# stm32-shield.net
KiCad netlist of a schematic drawn in EAGLE
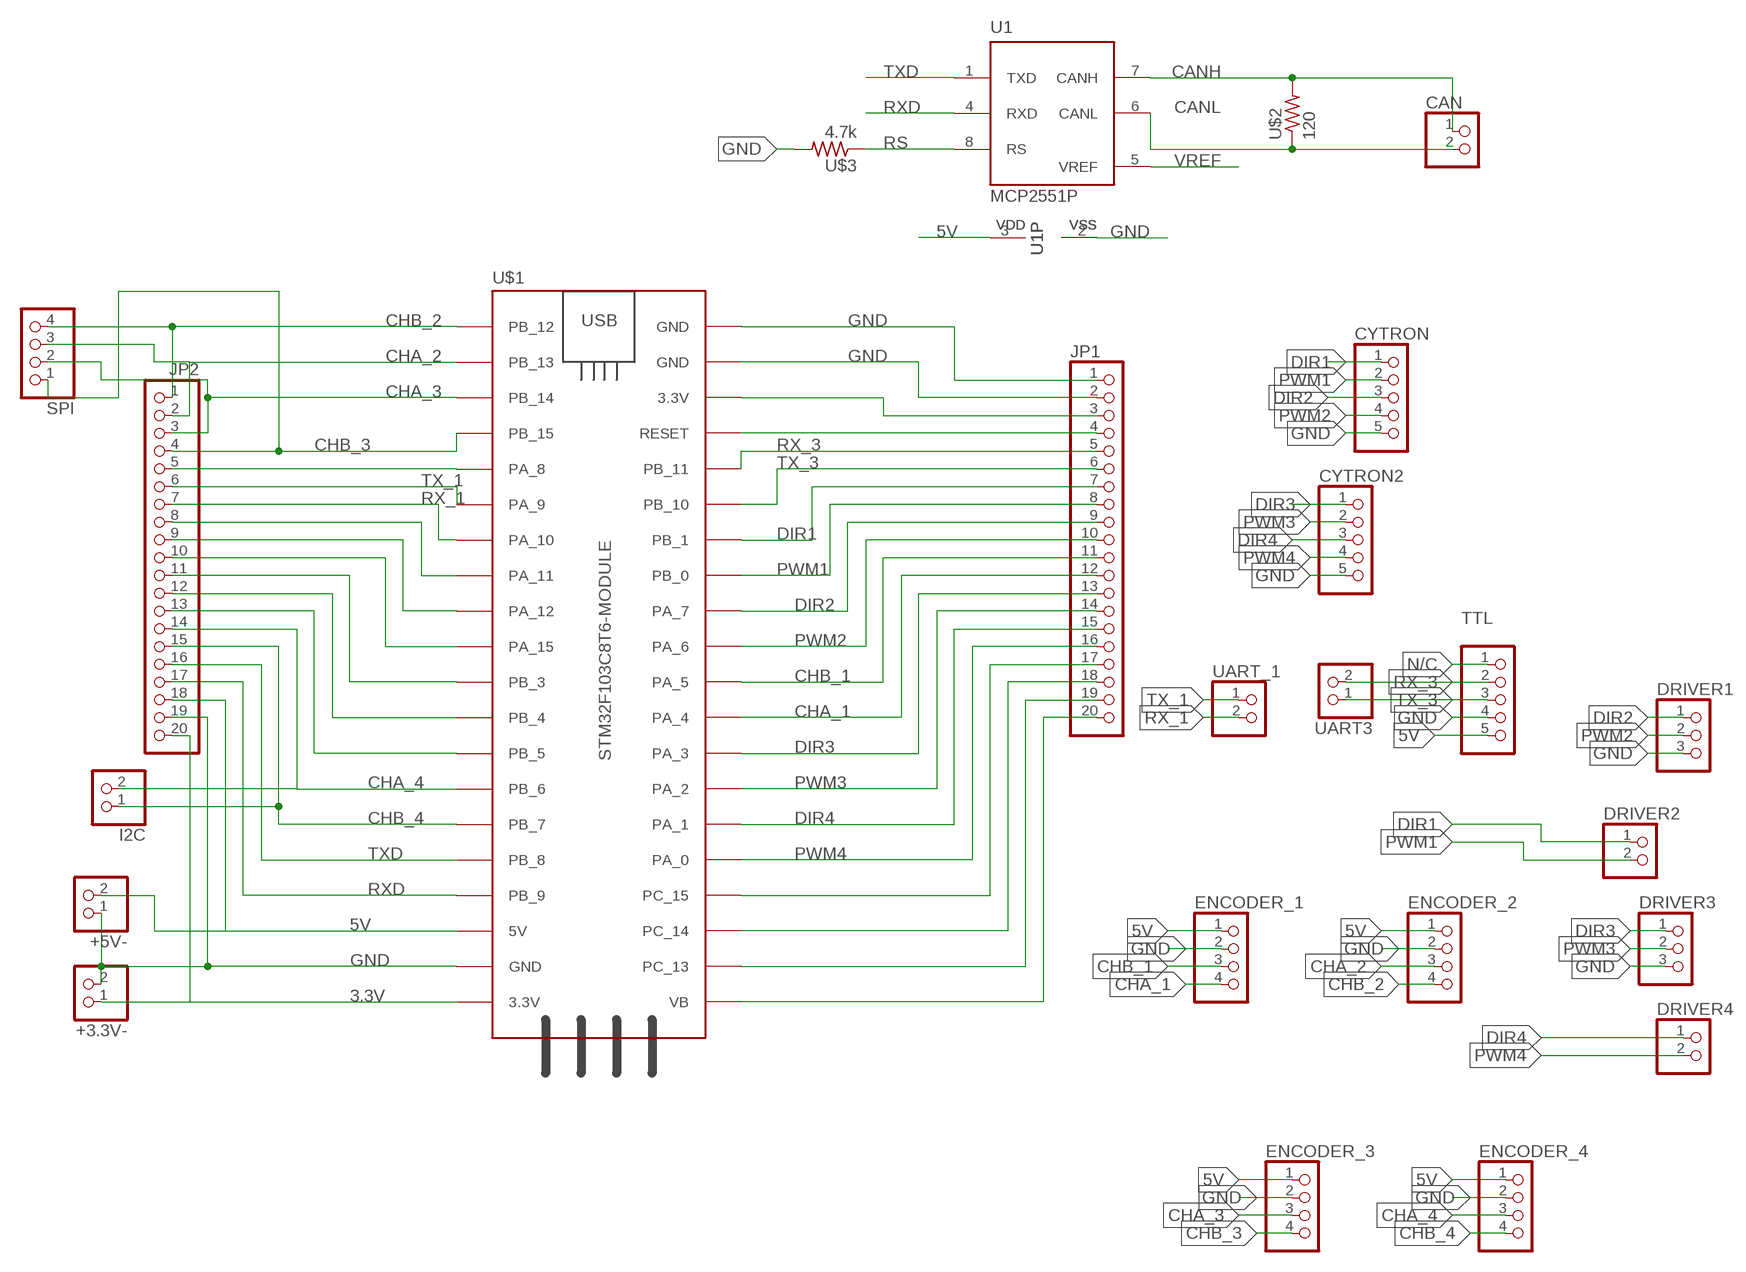
[diagram p0: schematic, sheet 1]

(export (version "E")
  (design (tool "Eeschema 10.0.6"))
  (components
    (comp (ref "+3.3V-")
      (value "PINHD-2_DATA")
      (footprint "eagle-import:1X02_DATA")
      (libsource (lib "eagle-import") (part "PINHD-2_DATA"))
    )
    (comp (ref "+5V-")
      (value "PINHD-2_DATA")
      (footprint "eagle-import:1X02_DATA")
      (libsource (lib "eagle-import") (part "PINHD-2_DATA"))
    )
    (comp (ref "CAN")
      (value "PINHD-2_DATA")
      (footprint "eagle-import:1X02_DATA")
      (libsource (lib "eagle-import") (part "PINHD-2_DATA"))
    )
    (comp (ref "CYTRON")
      (value "PINHD-5_DATA")
      (footprint "eagle-import:1X05_DATA")
      (libsource (lib "eagle-import") (part "PINHD-5_DATA"))
    )
    (comp (ref "CYTRON2")
      (value "PINHD-5_DATA")
      (footprint "eagle-import:1X05_DATA")
      (libsource (lib "eagle-import") (part "PINHD-5_DATA"))
    )
    (comp (ref "DRIVER1")
      (value "PINHD-3_DATA")
      (footprint "eagle-import:1X03_DATA")
      (libsource (lib "eagle-import") (part "PINHD-3_DATA"))
    )
    (comp (ref "DRIVER2")
      (value "PINHD-2_DATA")
      (footprint "eagle-import:1X02_DATA")
      (libsource (lib "eagle-import") (part "PINHD-2_DATA"))
    )
    (comp (ref "DRIVER3")
      (value "PINHD-3_DATA")
      (footprint "eagle-import:1X03_DATA")
      (libsource (lib "eagle-import") (part "PINHD-3_DATA"))
    )
    (comp (ref "DRIVER4")
      (value "PINHD-2_DATA")
      (footprint "eagle-import:1X02_DATA")
      (libsource (lib "eagle-import") (part "PINHD-2_DATA"))
    )
    (comp (ref "ENCODER_1")
      (value "PINHD-4_DATA")
      (footprint "eagle-import:1X04_DATA")
      (libsource (lib "eagle-import") (part "PINHD-4_DATA"))
    )
    (comp (ref "ENCODER_2")
      (value "PINHD-4_DATA")
      (footprint "eagle-import:1X04_DATA")
      (libsource (lib "eagle-import") (part "PINHD-4_DATA"))
    )
    (comp (ref "ENCODER_3")
      (value "PINHD-4_DATA")
      (footprint "eagle-import:1X04_DATA")
      (libsource (lib "eagle-import") (part "PINHD-4_DATA"))
    )
    (comp (ref "ENCODER_4")
      (value "PINHD-4_DATA")
      (footprint "eagle-import:1X04_DATA")
      (libsource (lib "eagle-import") (part "PINHD-4_DATA"))
    )
    (comp (ref "I2C")
      (value "PINHD-2_DATA")
      (footprint "eagle-import:1X02_DATA")
      (libsource (lib "eagle-import") (part "PINHD-2_DATA"))
    )
    (comp (ref "JP1")
      (value "PINHD-1X20")
      (footprint "eagle-import:1X20")
      (libsource (lib "eagle-import") (part "PINHD-1X20"))
    )
    (comp (ref "JP2")
      (value "PINHD-1X20")
      (footprint "eagle-import:1X20")
      (libsource (lib "eagle-import") (part "PINHD-1X20"))
    )
    (comp (ref "SPI")
      (value "PINHD-4_DATA")
      (footprint "eagle-import:1X04_DATA")
      (libsource (lib "eagle-import") (part "PINHD-4_DATA"))
    )
    (comp (ref "TTL")
      (value "PINHD-5_DATA")
      (footprint "eagle-import:1X05_DATA")
      (libsource (lib "eagle-import") (part "PINHD-5_DATA"))
    )
    (comp (ref "U$1")
      (value "STM32F103C8T6-MODULE")
      (footprint "eagle-import:STM32F103C8T6-MODULE")
      (libsource (lib "eagle-import") (part "STM32F103C8T6-MODULE"))
    )
    (comp (ref "U$2")
      (value "120")
      (footprint "eagle-import:0204_7")
      (libsource (lib "eagle-import") (part "RES-7"))
    )
    (comp (ref "U$3")
      (value "4.7k")
      (footprint "eagle-import:0204_7")
      (libsource (lib "eagle-import") (part "RES-7"))
    )
    (comp (ref "U1")
      (value "MCP2551P")
      (footprint "eagle-import:DIL8")
      (libsource (lib "eagle-import") (part "MCP2551P"))
    )
    (comp (ref "UART3")
      (value "PINHD-2_DATA")
      (footprint "eagle-import:1X02_DATA")
      (libsource (lib "eagle-import") (part "PINHD-2_DATA"))
    )
    (comp (ref "UART_1")
      (value "PINHD-2_DATA")
      (footprint "eagle-import:1X02_DATA")
      (libsource (lib "eagle-import") (part "PINHD-2_DATA"))
    )
  )
  (nets
    (net (code "1") (name "/3.3V") (class "Default")
      (node (ref "+3.3V-") (pin "1") (pinfunction "1_1") (pintype "passive"))
      (node (ref "JP2") (pin "20") (pinfunction "20_20") (pintype "passive"))
      (node (ref "U$1") (pin "3.3V_1") (pinfunction "3.3V_3.3V_1") (pintype "bidirectional"))
    )
    (net (code "2") (name "/CANH") (class "Default")
      (node (ref "CAN") (pin "1") (pinfunction "1_1") (pintype "passive"))
      (node (ref "U$2") (pin "2") (pinfunction "2_2") (pintype "passive"))
      (node (ref "U1") (pin "7") (pinfunction "CANH_7") (pintype "bidirectional"))
    )
    (net (code "3") (name "/CANL") (class "Default")
      (node (ref "CAN") (pin "2") (pinfunction "2_2") (pintype "passive"))
      (node (ref "U$2") (pin "1") (pinfunction "1_1") (pintype "passive"))
      (node (ref "U1") (pin "6") (pinfunction "CANL_6") (pintype "bidirectional"))
    )
    (net (code "4") (name "/RS") (class "Default")
      (node (ref "U$3") (pin "1") (pinfunction "1_1") (pintype "passive"))
      (node (ref "U1") (pin "8") (pinfunction "RS_8") (pintype "input"))
    )
    (net (code "5") (name "/RXD") (class "Default")
      (node (ref "JP2") (pin "17") (pinfunction "17_17") (pintype "passive"))
      (node (ref "U$1") (pin "PB_9") (pinfunction "PB_9_PB_9") (pintype "bidirectional"))
      (node (ref "U1") (pin "4") (pinfunction "RXD_4") (pintype "output"))
    )
    (net (code "6") (name "/TXD") (class "Default")
      (node (ref "JP2") (pin "16") (pinfunction "16_16") (pintype "passive"))
      (node (ref "U$1") (pin "PB_8") (pinfunction "PB_8_PB_8") (pintype "bidirectional"))
      (node (ref "U1") (pin "1") (pinfunction "TXD_1") (pintype "input"))
    )
    (net (code "7") (name "/VREF") (class "Default")
      (node (ref "U1") (pin "5") (pinfunction "VREF_5") (pintype "power_in"))
    )
    (net (code "8") (name "5V") (class "Default")
      (node (ref "+5V-") (pin "2") (pinfunction "2_2") (pintype "passive"))
      (node (ref "ENCODER_1") (pin "1") (pinfunction "1_1") (pintype "passive"))
      (node (ref "ENCODER_2") (pin "1") (pinfunction "1_1") (pintype "passive"))
      (node (ref "ENCODER_3") (pin "1") (pinfunction "1_1") (pintype "passive"))
      (node (ref "ENCODER_4") (pin "1") (pinfunction "1_1") (pintype "passive"))
      (node (ref "JP2") (pin "18") (pinfunction "18_18") (pintype "passive"))
      (node (ref "TTL") (pin "5") (pinfunction "5_5") (pintype "passive"))
      (node (ref "U$1") (pin "5V") (pinfunction "5V_5V") (pintype "bidirectional"))
      (node (ref "U1") (pin "3") (pinfunction "VDD_3") (pintype "power_in"))
    )
    (net (code "9") (name "CHA_1") (class "Default")
      (node (ref "ENCODER_1") (pin "4") (pinfunction "4_4") (pintype "passive"))
      (node (ref "JP1") (pin "12") (pinfunction "12_12") (pintype "passive"))
      (node (ref "U$1") (pin "PA_4") (pinfunction "PA_4_PA_4") (pintype "bidirectional"))
    )
    (net (code "10") (name "CHA_2") (class "Default")
      (node (ref "ENCODER_2") (pin "3") (pinfunction "3_3") (pintype "passive"))
      (node (ref "JP2") (pin "2") (pinfunction "2_2") (pintype "passive"))
      (node (ref "SPI") (pin "3") (pinfunction "3_3") (pintype "passive"))
      (node (ref "U$1") (pin "PB_13") (pinfunction "PB_13_PB_13") (pintype "bidirectional"))
    )
    (net (code "11") (name "CHA_3") (class "Default")
      (node (ref "ENCODER_3") (pin "3") (pinfunction "3_3") (pintype "passive"))
      (node (ref "JP2") (pin "3") (pinfunction "3_3") (pintype "passive"))
      (node (ref "SPI") (pin "2") (pinfunction "2_2") (pintype "passive"))
      (node (ref "U$1") (pin "PB_14") (pinfunction "PB_14_PB_14") (pintype "bidirectional"))
    )
    (net (code "12") (name "CHA_4") (class "Default")
      (node (ref "ENCODER_4") (pin "3") (pinfunction "3_3") (pintype "passive"))
      (node (ref "I2C") (pin "2") (pinfunction "2_2") (pintype "passive"))
      (node (ref "JP2") (pin "14") (pinfunction "14_14") (pintype "passive"))
      (node (ref "U$1") (pin "PB_6") (pinfunction "PB_6_PB_6") (pintype "bidirectional"))
    )
    (net (code "13") (name "CHB_1") (class "Default")
      (node (ref "ENCODER_1") (pin "3") (pinfunction "3_3") (pintype "passive"))
      (node (ref "JP1") (pin "11") (pinfunction "11_11") (pintype "passive"))
      (node (ref "U$1") (pin "PA_5") (pinfunction "PA_5_PA_5") (pintype "bidirectional"))
    )
    (net (code "14") (name "CHB_2") (class "Default")
      (node (ref "ENCODER_2") (pin "4") (pinfunction "4_4") (pintype "passive"))
      (node (ref "JP2") (pin "1") (pinfunction "1_1") (pintype "passive"))
      (node (ref "SPI") (pin "4") (pinfunction "4_4") (pintype "passive"))
      (node (ref "U$1") (pin "PB_12") (pinfunction "PB_12_PB_12") (pintype "bidirectional"))
    )
    (net (code "15") (name "CHB_3") (class "Default")
      (node (ref "ENCODER_3") (pin "4") (pinfunction "4_4") (pintype "passive"))
      (node (ref "JP2") (pin "4") (pinfunction "4_4") (pintype "passive"))
      (node (ref "SPI") (pin "1") (pinfunction "1_1") (pintype "passive"))
      (node (ref "U$1") (pin "PB_15") (pinfunction "PB_15_PB_15") (pintype "bidirectional"))
    )
    (net (code "16") (name "CHB_4") (class "Default")
      (node (ref "ENCODER_4") (pin "4") (pinfunction "4_4") (pintype "passive"))
      (node (ref "I2C") (pin "1") (pinfunction "1_1") (pintype "passive"))
      (node (ref "JP2") (pin "15") (pinfunction "15_15") (pintype "passive"))
      (node (ref "U$1") (pin "PB_7") (pinfunction "PB_7_PB_7") (pintype "bidirectional"))
    )
    (net (code "17") (name "DIR1") (class "Default")
      (node (ref "CYTRON") (pin "1") (pinfunction "1_1") (pintype "passive"))
      (node (ref "DRIVER2") (pin "1") (pinfunction "1_1") (pintype "passive"))
      (node (ref "JP1") (pin "7") (pinfunction "7_7") (pintype "passive"))
      (node (ref "U$1") (pin "PB_1") (pinfunction "PB_1_PB_1") (pintype "bidirectional"))
    )
    (net (code "18") (name "DIR2") (class "Default")
      (node (ref "CYTRON") (pin "3") (pinfunction "3_3") (pintype "passive"))
      (node (ref "DRIVER1") (pin "1") (pinfunction "1_1") (pintype "passive"))
      (node (ref "JP1") (pin "9") (pinfunction "9_9") (pintype "passive"))
      (node (ref "U$1") (pin "PA_7") (pinfunction "PA_7_PA_7") (pintype "bidirectional"))
    )
    (net (code "19") (name "DIR3") (class "Default")
      (node (ref "CYTRON2") (pin "1") (pinfunction "1_1") (pintype "passive"))
      (node (ref "DRIVER3") (pin "1") (pinfunction "1_1") (pintype "passive"))
      (node (ref "JP1") (pin "13") (pinfunction "13_13") (pintype "passive"))
      (node (ref "U$1") (pin "PA_3") (pinfunction "PA_3_PA_3") (pintype "bidirectional"))
    )
    (net (code "20") (name "DIR4") (class "Default")
      (node (ref "CYTRON2") (pin "3") (pinfunction "3_3") (pintype "passive"))
      (node (ref "DRIVER4") (pin "1") (pinfunction "1_1") (pintype "passive"))
      (node (ref "JP1") (pin "15") (pinfunction "15_15") (pintype "passive"))
      (node (ref "U$1") (pin "PA_1") (pinfunction "PA_1_PA_1") (pintype "bidirectional"))
    )
    (net (code "21") (name "GND") (class "Default")
      (node (ref "+3.3V-") (pin "2") (pinfunction "2_2") (pintype "passive"))
      (node (ref "+5V-") (pin "1") (pinfunction "1_1") (pintype "passive"))
      (node (ref "CYTRON") (pin "5") (pinfunction "5_5") (pintype "passive"))
      (node (ref "CYTRON2") (pin "5") (pinfunction "5_5") (pintype "passive"))
      (node (ref "DRIVER1") (pin "3") (pinfunction "3_3") (pintype "passive"))
      (node (ref "DRIVER3") (pin "3") (pinfunction "3_3") (pintype "passive"))
      (node (ref "ENCODER_1") (pin "2") (pinfunction "2_2") (pintype "passive"))
      (node (ref "ENCODER_2") (pin "2") (pinfunction "2_2") (pintype "passive"))
      (node (ref "ENCODER_3") (pin "2") (pinfunction "2_2") (pintype "passive"))
      (node (ref "ENCODER_4") (pin "2") (pinfunction "2_2") (pintype "passive"))
      (node (ref "JP1") (pin "1") (pinfunction "1_1") (pintype "passive"))
      (node (ref "JP1") (pin "2") (pinfunction "2_2") (pintype "passive"))
      (node (ref "JP2") (pin "19") (pinfunction "19_19") (pintype "passive"))
      (node (ref "TTL") (pin "4") (pinfunction "4_4") (pintype "passive"))
      (node (ref "U$1") (pin "GND_1") (pinfunction "GND_GND_1") (pintype "bidirectional"))
      (node (ref "U$1") (pin "GND_2") (pinfunction "GND_GND_2") (pintype "bidirectional"))
      (node (ref "U$1") (pin "GND_3") (pinfunction "GND_GND_3") (pintype "power_in"))
      (node (ref "U$3") (pin "2") (pinfunction "2_2") (pintype "passive"))
      (node (ref "U1") (pin "2") (pinfunction "VSS_2") (pintype "power_in"))
    )
    (net (code "22") (name "Net-(JP1-Pad3)") (class "Default")
      (node (ref "JP1") (pin "3") (pinfunction "3_3") (pintype "passive"))
      (node (ref "U$1") (pin "3.3V_2") (pinfunction "3.3V_3.3V_2") (pintype "bidirectional"))
    )
    (net (code "23") (name "Net-(JP1-Pad4)") (class "Default")
      (node (ref "JP1") (pin "4") (pinfunction "4_4") (pintype "passive"))
      (node (ref "U$1") (pin "RESET") (pinfunction "RESET_RESET") (pintype "bidirectional"))
    )
    (net (code "24") (name "Net-(JP1-Pad17)") (class "Default")
      (node (ref "JP1") (pin "17") (pinfunction "17_17") (pintype "passive"))
      (node (ref "U$1") (pin "PC_15") (pinfunction "PC_15_PC_15") (pintype "bidirectional"))
    )
    (net (code "25") (name "Net-(JP1-Pad18)") (class "Default")
      (node (ref "JP1") (pin "18") (pinfunction "18_18") (pintype "passive"))
      (node (ref "U$1") (pin "PC_14") (pinfunction "PC_14_PC_14") (pintype "bidirectional"))
    )
    (net (code "26") (name "Net-(JP1-Pad19)") (class "Default")
      (node (ref "JP1") (pin "19") (pinfunction "19_19") (pintype "passive"))
      (node (ref "U$1") (pin "PC_13") (pinfunction "PC_13_PC_13") (pintype "bidirectional"))
    )
    (net (code "27") (name "Net-(JP1-Pad20)") (class "Default")
      (node (ref "JP1") (pin "20") (pinfunction "20_20") (pintype "passive"))
      (node (ref "U$1") (pin "VB") (pinfunction "VB_VB") (pintype "bidirectional"))
    )
    (net (code "28") (name "Net-(JP2-Pad5)") (class "Default")
      (node (ref "JP2") (pin "5") (pinfunction "5_5") (pintype "passive"))
      (node (ref "U$1") (pin "PA_8") (pinfunction "PA_8_PA_8") (pintype "bidirectional"))
    )
    (net (code "29") (name "Net-(JP2-Pad8)") (class "Default")
      (node (ref "JP2") (pin "8") (pinfunction "8_8") (pintype "passive"))
      (node (ref "U$1") (pin "PA_11") (pinfunction "PA_11_PA_11") (pintype "bidirectional"))
    )
    (net (code "30") (name "Net-(JP2-Pad9)") (class "Default")
      (node (ref "JP2") (pin "9") (pinfunction "9_9") (pintype "passive"))
      (node (ref "U$1") (pin "PA_12") (pinfunction "PA_12_PA_12") (pintype "bidirectional"))
    )
    (net (code "31") (name "Net-(JP2-Pad10)") (class "Default")
      (node (ref "JP2") (pin "10") (pinfunction "10_10") (pintype "passive"))
      (node (ref "U$1") (pin "PA_15") (pinfunction "PA_15_PA_15") (pintype "bidirectional"))
    )
    (net (code "32") (name "Net-(JP2-Pad11)") (class "Default")
      (node (ref "JP2") (pin "11") (pinfunction "11_11") (pintype "passive"))
      (node (ref "U$1") (pin "PB_3") (pinfunction "PB_3_PB_3") (pintype "bidirectional"))
    )
    (net (code "33") (name "Net-(JP2-Pad12)") (class "Default")
      (node (ref "JP2") (pin "12") (pinfunction "12_12") (pintype "passive"))
      (node (ref "U$1") (pin "PB_4") (pinfunction "PB_4_PB_4") (pintype "bidirectional"))
    )
    (net (code "34") (name "Net-(JP2-Pad13)") (class "Default")
      (node (ref "JP2") (pin "13") (pinfunction "13_13") (pintype "passive"))
      (node (ref "U$1") (pin "PB_5") (pinfunction "PB_5_PB_5") (pintype "bidirectional"))
    )
    (net (code "35") (name "N{slash}C") (class "Default")
      (node (ref "TTL") (pin "1") (pinfunction "1_1") (pintype "passive"))
    )
    (net (code "36") (name "PWM1") (class "Default")
      (node (ref "CYTRON") (pin "2") (pinfunction "2_2") (pintype "passive"))
      (node (ref "DRIVER2") (pin "2") (pinfunction "2_2") (pintype "passive"))
      (node (ref "JP1") (pin "8") (pinfunction "8_8") (pintype "passive"))
      (node (ref "U$1") (pin "PB_0") (pinfunction "PB_0_PB_0") (pintype "bidirectional"))
    )
    (net (code "37") (name "PWM2") (class "Default")
      (node (ref "CYTRON") (pin "4") (pinfunction "4_4") (pintype "passive"))
      (node (ref "DRIVER1") (pin "2") (pinfunction "2_2") (pintype "passive"))
      (node (ref "JP1") (pin "10") (pinfunction "10_10") (pintype "passive"))
      (node (ref "U$1") (pin "PA_6") (pinfunction "PA_6_PA_6") (pintype "bidirectional"))
    )
    (net (code "38") (name "PWM3") (class "Default")
      (node (ref "CYTRON2") (pin "2") (pinfunction "2_2") (pintype "passive"))
      (node (ref "DRIVER3") (pin "2") (pinfunction "2_2") (pintype "passive"))
      (node (ref "JP1") (pin "14") (pinfunction "14_14") (pintype "passive"))
      (node (ref "U$1") (pin "PA_2") (pinfunction "PA_2_PA_2") (pintype "bidirectional"))
    )
    (net (code "39") (name "PWM4") (class "Default")
      (node (ref "CYTRON2") (pin "4") (pinfunction "4_4") (pintype "passive"))
      (node (ref "DRIVER4") (pin "2") (pinfunction "2_2") (pintype "passive"))
      (node (ref "JP1") (pin "16") (pinfunction "16_16") (pintype "passive"))
      (node (ref "U$1") (pin "PA_0") (pinfunction "PA_0_PA_0") (pintype "bidirectional"))
    )
    (net (code "40") (name "RX_1") (class "Default")
      (node (ref "JP2") (pin "7") (pinfunction "7_7") (pintype "passive"))
      (node (ref "U$1") (pin "PA_10") (pinfunction "PA_10_PA_10") (pintype "bidirectional"))
      (node (ref "UART_1") (pin "2") (pinfunction "2_2") (pintype "passive"))
    )
    (net (code "41") (name "RX_3") (class "Default")
      (node (ref "JP1") (pin "5") (pinfunction "5_5") (pintype "passive"))
      (node (ref "TTL") (pin "2") (pinfunction "2_2") (pintype "passive"))
      (node (ref "U$1") (pin "PB_11") (pinfunction "PB_11_PB_11") (pintype "bidirectional"))
      (node (ref "UART3") (pin "2") (pinfunction "2_2") (pintype "passive"))
    )
    (net (code "42") (name "TX_1") (class "Default")
      (node (ref "JP2") (pin "6") (pinfunction "6_6") (pintype "passive"))
      (node (ref "U$1") (pin "PA_9") (pinfunction "PA_9_PA_9") (pintype "bidirectional"))
      (node (ref "UART_1") (pin "1") (pinfunction "1_1") (pintype "passive"))
    )
    (net (code "43") (name "TX_3") (class "Default")
      (node (ref "JP1") (pin "6") (pinfunction "6_6") (pintype "passive"))
      (node (ref "TTL") (pin "3") (pinfunction "3_3") (pintype "passive"))
      (node (ref "U$1") (pin "PB_10") (pinfunction "PB_10_PB_10") (pintype "bidirectional"))
      (node (ref "UART3") (pin "1") (pinfunction "1_1") (pintype "passive"))
    )
  )
)
